# 8-8main.net
KiCad netlist of a schematic drawn in Altium Designer
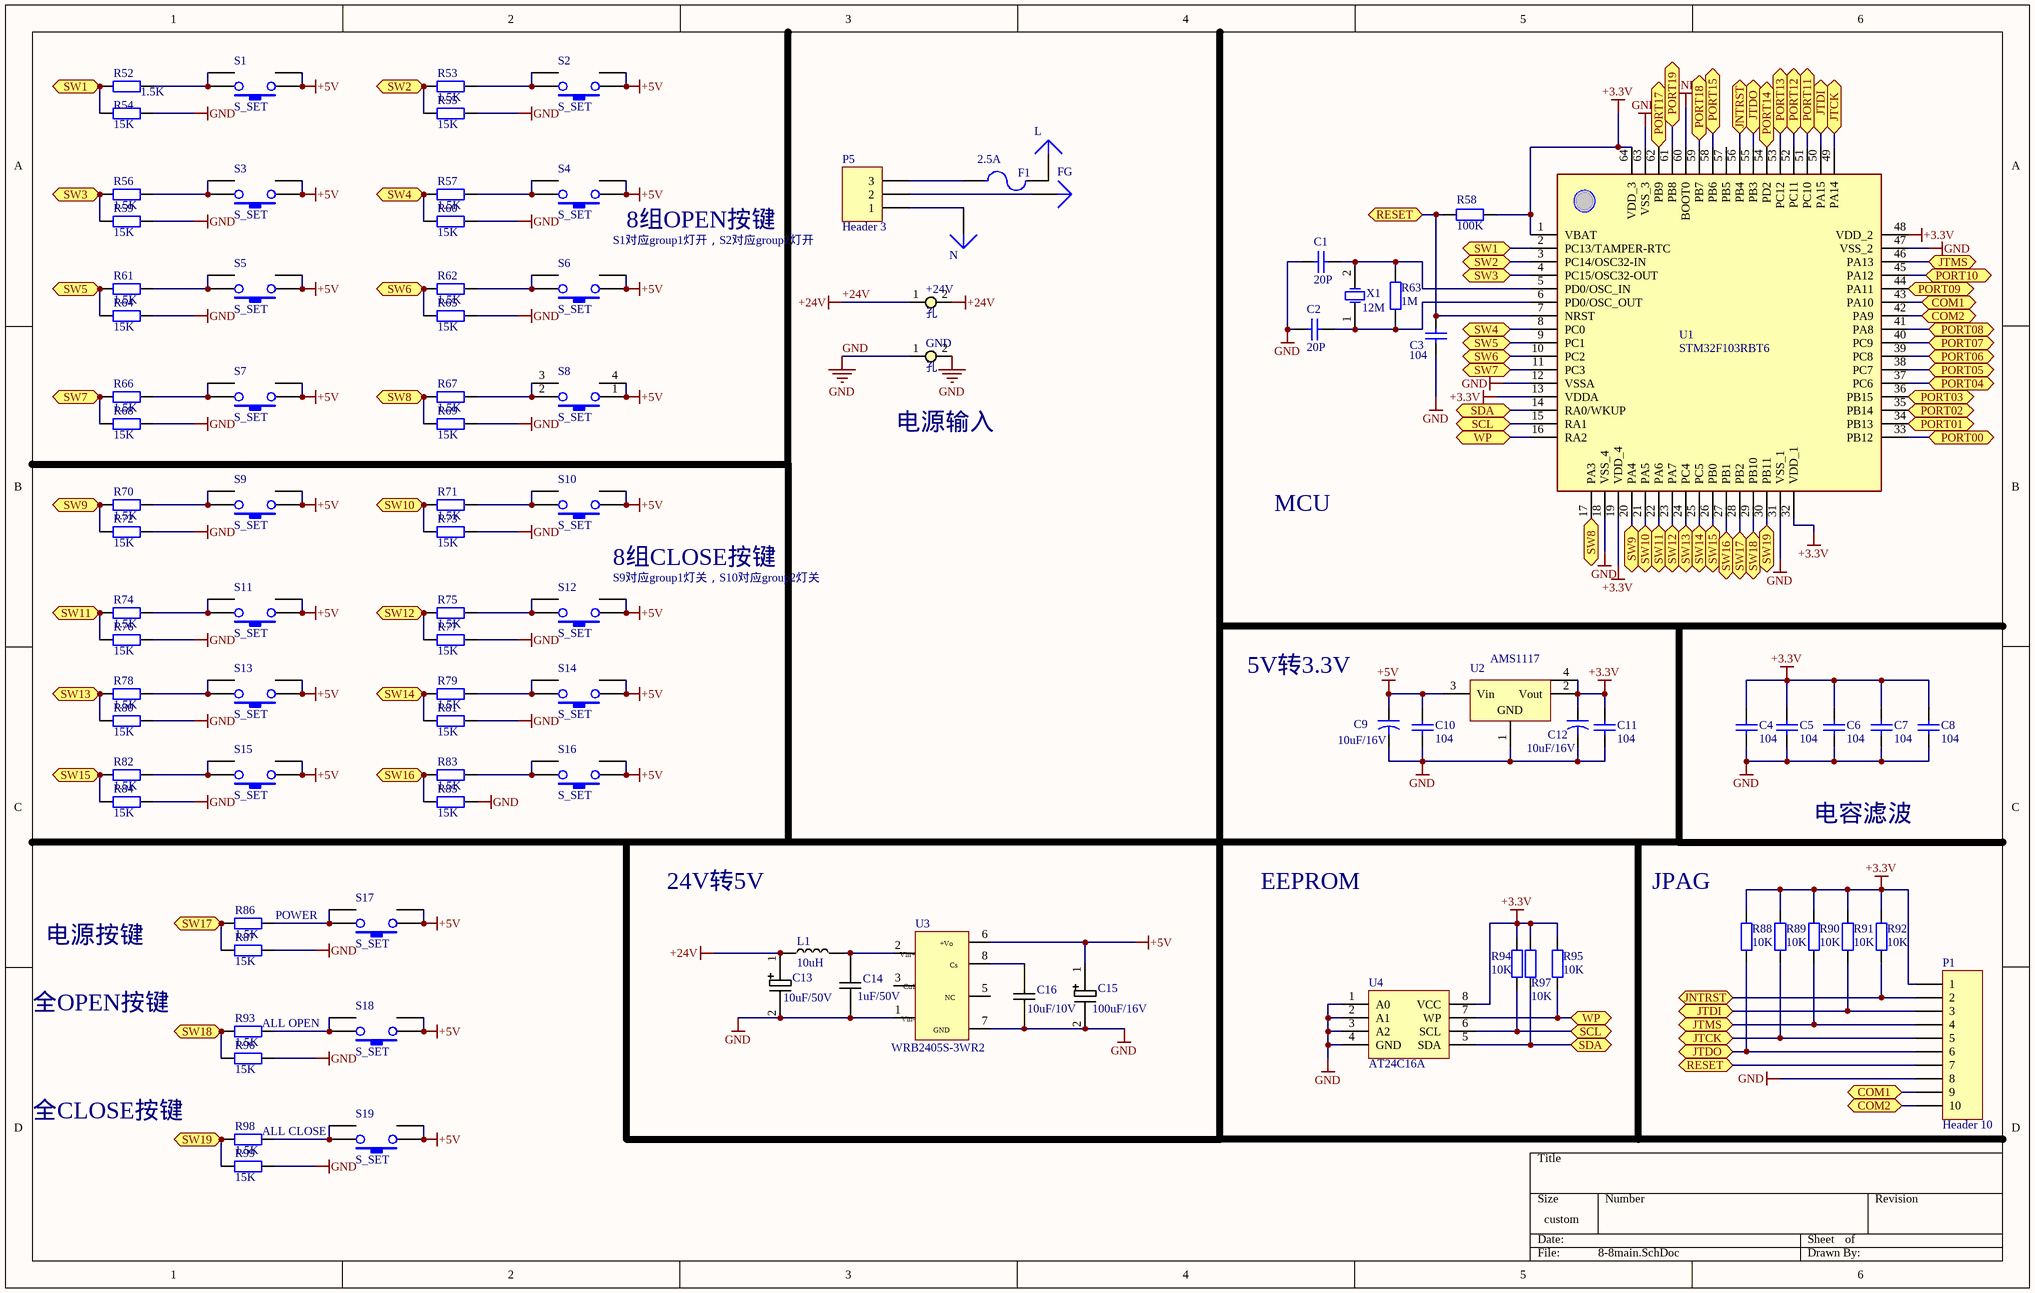
[diagram p0: 8-8main.SchDoc]

(export (version "E")
  (design (tool "Eeschema 10.0.6"))
  (components
    (comp (ref "+24V") (value "孔") (footprint "TIMECON2PIN5.1MMA") (libsource (lib "mylib") (part "安装孔3")))
    (comp (ref "C1")
      (value "20P")
      (footprint "0805 C")
      (description "Capacitor")
      (fields
        (field (name "MANUFACTURER") "Generic Components")
        (field (name "Comment") "Cap")
        (field (name "PUBLISHER") "Altium Hobart Technology Centre")
      )
      (libsource (lib "Miscellaneous Devices") (part "Cap"))
    )
    (comp (ref "C2")
      (value "20P")
      (footprint "0805 C")
      (description "Capacitor")
      (fields
        (field (name "MANUFACTURER") "Generic Components")
        (field (name "Comment") "Cap")
        (field (name "PUBLISHER") "Altium Hobart Technology Centre")
      )
      (libsource (lib "Miscellaneous Devices") (part "Cap"))
    )
    (comp (ref "C3")
      (value "104")
      (footprint "0805 C")
      (description "Capacitor")
      (fields
        (field (name "MANUFACTURER") "Generic Components")
        (field (name "Comment") "Cap")
        (field (name "PUBLISHER") "Altium Hobart Technology Centre")
      )
      (libsource (lib "Miscellaneous Devices") (part "Cap"))
    )
    (comp (ref "C4")
      (value "104")
      (footprint "0603 C")
      (description "Capacitor")
      (fields
        (field (name "MANUFACTURER") "Generic Components")
        (field (name "Comment") "Cap")
        (field (name "PUBLISHER") "Altium Hobart Technology Centre")
      )
      (libsource (lib "Miscellaneous Devices") (part "Cap"))
    )
    (comp (ref "C5")
      (value "104")
      (footprint "0603 C")
      (description "Capacitor")
      (fields
        (field (name "MANUFACTURER") "Generic Components")
        (field (name "Comment") "Cap")
        (field (name "PUBLISHER") "Altium Hobart Technology Centre")
      )
      (libsource (lib "Miscellaneous Devices") (part "Cap"))
    )
    (comp (ref "C6")
      (value "104")
      (footprint "0603 C")
      (description "Capacitor")
      (fields
        (field (name "MANUFACTURER") "Generic Components")
        (field (name "Comment") "Cap")
        (field (name "PUBLISHER") "Altium Hobart Technology Centre")
      )
      (libsource (lib "Miscellaneous Devices") (part "Cap"))
    )
    (comp (ref "C7")
      (value "104")
      (footprint "0603 C")
      (description "Capacitor")
      (fields
        (field (name "MANUFACTURER") "Generic Components")
        (field (name "Comment") "Cap")
        (field (name "PUBLISHER") "Altium Hobart Technology Centre")
      )
      (libsource (lib "Miscellaneous Devices") (part "Cap"))
    )
    (comp (ref "C8")
      (value "104")
      (footprint "0603 C")
      (description "Capacitor")
      (fields
        (field (name "MANUFACTURER") "Generic Components")
        (field (name "Comment") "Cap")
        (field (name "PUBLISHER") "Altium Hobart Technology Centre")
      )
      (libsource (lib "Miscellaneous Devices") (part "Cap"))
    )
    (comp (ref "C9")
      (value "10uF/16V")
      (footprint "0805 C")
      (description "Capacitor")
      (fields (field (name "PUBLISHER") "Altium Limited"))
      (libsource (lib "Miscellaneous Devices") (part "Cap2"))
    )
    (comp (ref "C10")
      (value "104")
      (footprint "0805 C")
      (description "Capacitor")
      (fields
        (field (name "MANUFACTURER") "Generic Components")
        (field (name "Comment") "Cap")
        (field (name "PUBLISHER") "Altium Hobart Technology Centre")
      )
      (libsource (lib "Miscellaneous Devices") (part "Cap"))
    )
    (comp (ref "C11")
      (value "104")
      (footprint "0805 C")
      (description "Capacitor")
      (fields
        (field (name "MANUFACTURER") "Generic Components")
        (field (name "Comment") "Cap")
        (field (name "PUBLISHER") "Altium Hobart Technology Centre")
      )
      (libsource (lib "Miscellaneous Devices") (part "Cap"))
    )
    (comp (ref "C12")
      (value "10uF/16V")
      (footprint "0805 C")
      (description "Capacitor")
      (fields (field (name "PUBLISHER") "Altium Limited"))
      (libsource (lib "Miscellaneous Devices") (part "Cap2"))
    )
    (comp (ref "C13")
      (value "10uF/50V")
      (footprint "C 10uF/50V")
      (fields (field (name "Comment") "CAP Al"))
      (libsource (lib "mylib") (part "CAP Al"))
    )
    (comp (ref "C14")
      (value "1uF/50V")
      (footprint "0805 C")
      (fields (field (name "Comment") "CAP"))
      (libsource (lib "mylib") (part "CAP"))
    )
    (comp (ref "C15")
      (value "100uF/16V")
      (footprint "C 100uF/16V φ5*11mm SIP")
      (fields (field (name "Comment") "CAP Al"))
      (libsource (lib "mylib") (part "CAP Al"))
    )
    (comp (ref "C16")
      (value "10uF/10V")
      (footprint "0805 C")
      (fields (field (name "Comment") "CAP"))
      (libsource (lib "mylib") (part "CAP"))
    )
    (comp (ref "F1")
      (value "2.5A")
      (footprint "1A/250V-1")
      (description "Fuse")
      (fields (field (name "PUBLISHER") "Altium Limited"))
      (libsource (lib "Miscellaneous Devices") (part "Fuse 2"))
    )
    (comp (ref "FG") (value "~") (footprint "VIA") (libsource (lib "*") (part "PLUG")))
    (comp (ref "GND") (value "孔") (footprint "TIMECON2PIN5.1MMA") (libsource (lib "mylib") (part "安装孔3")))
    (comp (ref "L") (value "~") (footprint "VIA") (libsource (lib "*") (part "PLUG")))
    (comp (ref "L1")
      (value "10uH")
      (footprint "L 2.2uH SMD")
      (fields (field (name "Comment") "Inductor"))
      (libsource (lib "mylib") (part "Inductor"))
    )
    (comp (ref "N") (value "~") (footprint "VIA") (libsource (lib "*") (part "PLUG")))
    (comp (ref "P1")
      (value "Header 10")
      (footprint "Header 2*5 SMD")
      (description "Header, 10-Pin")
      (fields (field (name "PUBLISHER") "Altium Limited"))
      (libsource (lib "Miscellaneous Connectors") (part "Header 10"))
    )
    (comp (ref "P5")
      (value "Header 3")
      (footprint "TIMECON3PIN5.1MMA")
      (description "Header, 3-Pin")
      (fields (field (name "PUBLISHER") "Altium Limited"))
      (libsource (lib "Miscellaneous Connectors") (part "Header 3"))
    )
    (comp (ref "R52")
      (value "1.5K")
      (footprint "0805 R 1/8W")
      (description "Resistor")
      (fields
        (field (name "MANUFACTURER") "Generic Components")
        (field (name "Comment") "Res2")
        (field (name "PUBLISHER") "Altium Hobart Technology Centre")
      )
      (libsource (lib "Miscellaneous Devices") (part "Res2"))
    )
    (comp (ref "R53")
      (value "1.5K")
      (footprint "0805 R 1/8W")
      (description "Resistor")
      (fields
        (field (name "MANUFACTURER") "Generic Components")
        (field (name "Comment") "Res2")
        (field (name "PUBLISHER") "Altium Hobart Technology Centre")
      )
      (libsource (lib "Miscellaneous Devices") (part "Res2"))
    )
    (comp (ref "R54")
      (value "15K")
      (footprint "0805 R 1/8W")
      (description "Resistor")
      (fields
        (field (name "MANUFACTURER") "Generic Components")
        (field (name "Comment") "Res2")
        (field (name "PUBLISHER") "Altium Hobart Technology Centre")
      )
      (libsource (lib "Miscellaneous Devices") (part "Res2"))
    )
    (comp (ref "R55")
      (value "15K")
      (footprint "0805 R 1/8W")
      (description "Resistor")
      (fields
        (field (name "MANUFACTURER") "Generic Components")
        (field (name "Comment") "Res2")
        (field (name "PUBLISHER") "Altium Hobart Technology Centre")
      )
      (libsource (lib "Miscellaneous Devices") (part "Res2"))
    )
    (comp (ref "R56")
      (value "1.5K")
      (footprint "0805 R 1/8W")
      (description "Resistor")
      (fields
        (field (name "MANUFACTURER") "Generic Components")
        (field (name "Comment") "Res2")
        (field (name "PUBLISHER") "Altium Hobart Technology Centre")
      )
      (libsource (lib "Miscellaneous Devices") (part "Res2"))
    )
    (comp (ref "R57")
      (value "1.5K")
      (footprint "0805 R 1/8W")
      (description "Resistor")
      (fields
        (field (name "MANUFACTURER") "Generic Components")
        (field (name "Comment") "Res2")
        (field (name "PUBLISHER") "Altium Hobart Technology Centre")
      )
      (libsource (lib "Miscellaneous Devices") (part "Res2"))
    )
    (comp (ref "R58")
      (value "100K")
      (footprint "0805 R 1/8W")
      (description "Resistor")
      (fields
        (field (name "MANUFACTURER") "Generic Components")
        (field (name "Comment") "Res2")
        (field (name "PUBLISHER") "Altium Hobart Technology Centre")
      )
      (libsource (lib "") (part "Res2_3"))
    )
    (comp (ref "R59")
      (value "15K")
      (footprint "0805 R 1/8W")
      (description "Resistor")
      (fields
        (field (name "MANUFACTURER") "Generic Components")
        (field (name "Comment") "Res2")
        (field (name "PUBLISHER") "Altium Hobart Technology Centre")
      )
      (libsource (lib "Miscellaneous Devices") (part "Res2"))
    )
    (comp (ref "R60")
      (value "15K")
      (footprint "0805 R 1/8W")
      (description "Resistor")
      (fields
        (field (name "MANUFACTURER") "Generic Components")
        (field (name "Comment") "Res2")
        (field (name "PUBLISHER") "Altium Hobart Technology Centre")
      )
      (libsource (lib "Miscellaneous Devices") (part "Res2"))
    )
    (comp (ref "R61")
      (value "1.5K")
      (footprint "0805 R 1/8W")
      (description "Resistor")
      (fields
        (field (name "MANUFACTURER") "Generic Components")
        (field (name "Comment") "Res2")
        (field (name "PUBLISHER") "Altium Hobart Technology Centre")
      )
      (libsource (lib "Miscellaneous Devices") (part "Res2"))
    )
    (comp (ref "R62")
      (value "1.5K")
      (footprint "0805 R 1/8W")
      (description "Resistor")
      (fields
        (field (name "MANUFACTURER") "Generic Components")
        (field (name "Comment") "Res2")
        (field (name "PUBLISHER") "Altium Hobart Technology Centre")
      )
      (libsource (lib "Miscellaneous Devices") (part "Res2"))
    )
    (comp (ref "R63")
      (value "1M")
      (footprint "0805 R 1/8W")
      (description "Resistor")
      (fields
        (field (name "MANUFACTURER") "Generic Components")
        (field (name "Comment") "Res2")
        (field (name "PUBLISHER") "Altium Hobart Technology Centre")
      )
      (libsource (lib "") (part "Res2_2"))
    )
    (comp (ref "R64")
      (value "15K")
      (footprint "0805 R 1/8W")
      (description "Resistor")
      (fields
        (field (name "MANUFACTURER") "Generic Components")
        (field (name "Comment") "Res2")
        (field (name "PUBLISHER") "Altium Hobart Technology Centre")
      )
      (libsource (lib "Miscellaneous Devices") (part "Res2"))
    )
    (comp (ref "R65")
      (value "15K")
      (footprint "0805 R 1/8W")
      (description "Resistor")
      (fields
        (field (name "MANUFACTURER") "Generic Components")
        (field (name "Comment") "Res2")
        (field (name "PUBLISHER") "Altium Hobart Technology Centre")
      )
      (libsource (lib "Miscellaneous Devices") (part "Res2"))
    )
    (comp (ref "R66")
      (value "1.5K")
      (footprint "0805 R 1/8W")
      (description "Resistor")
      (fields
        (field (name "MANUFACTURER") "Generic Components")
        (field (name "Comment") "Res2")
        (field (name "PUBLISHER") "Altium Hobart Technology Centre")
      )
      (libsource (lib "Miscellaneous Devices") (part "Res2"))
    )
    (comp (ref "R67")
      (value "1.5K")
      (footprint "0805 R 1/8W")
      (description "Resistor")
      (fields
        (field (name "MANUFACTURER") "Generic Components")
        (field (name "Comment") "Res2")
        (field (name "PUBLISHER") "Altium Hobart Technology Centre")
      )
      (libsource (lib "Miscellaneous Devices") (part "Res2"))
    )
    (comp (ref "R68")
      (value "15K")
      (footprint "0805 R 1/8W")
      (description "Resistor")
      (fields
        (field (name "MANUFACTURER") "Generic Components")
        (field (name "Comment") "Res2")
        (field (name "PUBLISHER") "Altium Hobart Technology Centre")
      )
      (libsource (lib "Miscellaneous Devices") (part "Res2"))
    )
    (comp (ref "R69")
      (value "15K")
      (footprint "0805 R 1/8W")
      (description "Resistor")
      (fields
        (field (name "MANUFACTURER") "Generic Components")
        (field (name "Comment") "Res2")
        (field (name "PUBLISHER") "Altium Hobart Technology Centre")
      )
      (libsource (lib "Miscellaneous Devices") (part "Res2"))
    )
    (comp (ref "R70")
      (value "1.5K")
      (footprint "0805 R 1/8W")
      (description "Resistor")
      (fields
        (field (name "MANUFACTURER") "Generic Components")
        (field (name "Comment") "Res2")
        (field (name "PUBLISHER") "Altium Hobart Technology Centre")
      )
      (libsource (lib "Miscellaneous Devices") (part "Res2"))
    )
    (comp (ref "R71")
      (value "1.5K")
      (footprint "0805 R 1/8W")
      (description "Resistor")
      (fields
        (field (name "MANUFACTURER") "Generic Components")
        (field (name "Comment") "Res2")
        (field (name "PUBLISHER") "Altium Hobart Technology Centre")
      )
      (libsource (lib "Miscellaneous Devices") (part "Res2"))
    )
    (comp (ref "R72")
      (value "15K")
      (footprint "0805 R 1/8W")
      (description "Resistor")
      (fields
        (field (name "MANUFACTURER") "Generic Components")
        (field (name "Comment") "Res2")
        (field (name "PUBLISHER") "Altium Hobart Technology Centre")
      )
      (libsource (lib "Miscellaneous Devices") (part "Res2"))
    )
    (comp (ref "R73")
      (value "15K")
      (footprint "0805 R 1/8W")
      (description "Resistor")
      (fields
        (field (name "MANUFACTURER") "Generic Components")
        (field (name "Comment") "Res2")
        (field (name "PUBLISHER") "Altium Hobart Technology Centre")
      )
      (libsource (lib "Miscellaneous Devices") (part "Res2"))
    )
    (comp (ref "R74")
      (value "1.5K")
      (footprint "0805 R 1/8W")
      (description "Resistor")
      (fields
        (field (name "MANUFACTURER") "Generic Components")
        (field (name "Comment") "Res2")
        (field (name "PUBLISHER") "Altium Hobart Technology Centre")
      )
      (libsource (lib "Miscellaneous Devices") (part "Res2"))
    )
    (comp (ref "R75")
      (value "1.5K")
      (footprint "0805 R 1/8W")
      (description "Resistor")
      (fields
        (field (name "MANUFACTURER") "Generic Components")
        (field (name "Comment") "Res2")
        (field (name "PUBLISHER") "Altium Hobart Technology Centre")
      )
      (libsource (lib "Miscellaneous Devices") (part "Res2"))
    )
    (comp (ref "R76")
      (value "15K")
      (footprint "0805 R 1/8W")
      (description "Resistor")
      (fields
        (field (name "MANUFACTURER") "Generic Components")
        (field (name "Comment") "Res2")
        (field (name "PUBLISHER") "Altium Hobart Technology Centre")
      )
      (libsource (lib "Miscellaneous Devices") (part "Res2"))
    )
    (comp (ref "R77")
      (value "15K")
      (footprint "0805 R 1/8W")
      (description "Resistor")
      (fields
        (field (name "MANUFACTURER") "Generic Components")
        (field (name "Comment") "Res2")
        (field (name "PUBLISHER") "Altium Hobart Technology Centre")
      )
      (libsource (lib "Miscellaneous Devices") (part "Res2"))
    )
    (comp (ref "R78")
      (value "1.5K")
      (footprint "0805 R 1/8W")
      (description "Resistor")
      (fields
        (field (name "MANUFACTURER") "Generic Components")
        (field (name "Comment") "Res2")
        (field (name "PUBLISHER") "Altium Hobart Technology Centre")
      )
      (libsource (lib "Miscellaneous Devices") (part "Res2"))
    )
    (comp (ref "R79")
      (value "1.5K")
      (footprint "0805 R 1/8W")
      (description "Resistor")
      (fields
        (field (name "MANUFACTURER") "Generic Components")
        (field (name "Comment") "Res2")
        (field (name "PUBLISHER") "Altium Hobart Technology Centre")
      )
      (libsource (lib "Miscellaneous Devices") (part "Res2"))
    )
    (comp (ref "R80")
      (value "15K")
      (footprint "0805 R 1/8W")
      (description "Resistor")
      (fields
        (field (name "MANUFACTURER") "Generic Components")
        (field (name "Comment") "Res2")
        (field (name "PUBLISHER") "Altium Hobart Technology Centre")
      )
      (libsource (lib "Miscellaneous Devices") (part "Res2"))
    )
    (comp (ref "R81")
      (value "15K")
      (footprint "0805 R 1/8W")
      (description "Resistor")
      (fields
        (field (name "MANUFACTURER") "Generic Components")
        (field (name "Comment") "Res2")
        (field (name "PUBLISHER") "Altium Hobart Technology Centre")
      )
      (libsource (lib "Miscellaneous Devices") (part "Res2"))
    )
    (comp (ref "R82")
      (value "1.5K")
      (footprint "0805 R 1/8W")
      (description "Resistor")
      (fields
        (field (name "MANUFACTURER") "Generic Components")
        (field (name "Comment") "Res2")
        (field (name "PUBLISHER") "Altium Hobart Technology Centre")
      )
      (libsource (lib "Miscellaneous Devices") (part "Res2"))
    )
    (comp (ref "R83")
      (value "1.5K")
      (footprint "0805 R 1/8W")
      (description "Resistor")
      (fields
        (field (name "MANUFACTURER") "Generic Components")
        (field (name "Comment") "Res2")
        (field (name "PUBLISHER") "Altium Hobart Technology Centre")
      )
      (libsource (lib "Miscellaneous Devices") (part "Res2"))
    )
    (comp (ref "R84")
      (value "15K")
      (footprint "0805 R 1/8W")
      (description "Resistor")
      (fields
        (field (name "MANUFACTURER") "Generic Components")
        (field (name "Comment") "Res2")
        (field (name "PUBLISHER") "Altium Hobart Technology Centre")
      )
      (libsource (lib "Miscellaneous Devices") (part "Res2"))
    )
    (comp (ref "R85")
      (value "15K")
      (footprint "0805 R 1/8W")
      (description "Resistor")
      (fields
        (field (name "MANUFACTURER") "Generic Components")
        (field (name "Comment") "Res2")
        (field (name "PUBLISHER") "Altium Hobart Technology Centre")
      )
      (libsource (lib "Miscellaneous Devices") (part "Res2"))
    )
    (comp (ref "R86")
      (value "1.5K")
      (footprint "0805 R 1/8W")
      (description "Resistor")
      (fields
        (field (name "MANUFACTURER") "Generic Components")
        (field (name "Comment") "Res2")
        (field (name "PUBLISHER") "Altium Hobart Technology Centre")
      )
      (libsource (lib "Miscellaneous Devices") (part "Res2"))
    )
    (comp (ref "R87")
      (value "15K")
      (footprint "0805 R 1/8W")
      (description "Resistor")
      (fields
        (field (name "MANUFACTURER") "Generic Components")
        (field (name "Comment") "Res2")
        (field (name "PUBLISHER") "Altium Hobart Technology Centre")
      )
      (libsource (lib "Miscellaneous Devices") (part "Res2"))
    )
    (comp (ref "R88")
      (value "10K")
      (footprint "0805 R 1/8W")
      (description "Resistor")
      (fields
        (field (name "MANUFACTURER") "Generic Components")
        (field (name "Comment") "Res2")
        (field (name "PUBLISHER") "Altium Hobart Technology Centre")
      )
      (libsource (lib "") (part "Res2_1"))
    )
    (comp (ref "R89")
      (value "10K")
      (footprint "0805 R 1/8W")
      (description "Resistor")
      (fields
        (field (name "MANUFACTURER") "Generic Components")
        (field (name "Comment") "Res2")
        (field (name "PUBLISHER") "Altium Hobart Technology Centre")
      )
      (libsource (lib "") (part "Res2_1"))
    )
    (comp (ref "R90")
      (value "10K")
      (footprint "0805 R 1/8W")
      (description "Resistor")
      (fields
        (field (name "MANUFACTURER") "Generic Components")
        (field (name "Comment") "Res2")
        (field (name "PUBLISHER") "Altium Hobart Technology Centre")
      )
      (libsource (lib "") (part "Res2_1"))
    )
    (comp (ref "R91")
      (value "10K")
      (footprint "0805 R 1/8W")
      (description "Resistor")
      (fields
        (field (name "MANUFACTURER") "Generic Components")
        (field (name "Comment") "Res2")
        (field (name "PUBLISHER") "Altium Hobart Technology Centre")
      )
      (libsource (lib "") (part "Res2_1"))
    )
    (comp (ref "R92")
      (value "10K")
      (footprint "0805 R 1/8W")
      (description "Resistor")
      (fields
        (field (name "MANUFACTURER") "Generic Components")
        (field (name "Comment") "Res2")
        (field (name "PUBLISHER") "Altium Hobart Technology Centre")
      )
      (libsource (lib "") (part "Res2_1"))
    )
    (comp (ref "R93")
      (value "1.5K")
      (footprint "0805 R 1/8W")
      (description "Resistor")
      (fields
        (field (name "MANUFACTURER") "Generic Components")
        (field (name "Comment") "Res2")
        (field (name "PUBLISHER") "Altium Hobart Technology Centre")
      )
      (libsource (lib "Miscellaneous Devices") (part "Res2"))
    )
    (comp (ref "R94")
      (value "10K")
      (footprint "0805 R 1/8W")
      (description "Resistor")
      (fields
        (field (name "MANUFACTURER") "Generic Components")
        (field (name "Comment") "Res2")
        (field (name "PUBLISHER") "Altium Hobart Technology Centre")
      )
      (libsource (lib "") (part "Res2_1"))
    )
    (comp (ref "R95")
      (value "10K")
      (footprint "0805 R 1/8W")
      (description "Resistor")
      (fields
        (field (name "MANUFACTURER") "Generic Components")
        (field (name "Comment") "Res2")
        (field (name "PUBLISHER") "Altium Hobart Technology Centre")
      )
      (libsource (lib "") (part "Res2_1"))
    )
    (comp (ref "R96")
      (value "15K")
      (footprint "0805 R 1/8W")
      (description "Resistor")
      (fields
        (field (name "MANUFACTURER") "Generic Components")
        (field (name "Comment") "Res2")
        (field (name "PUBLISHER") "Altium Hobart Technology Centre")
      )
      (libsource (lib "Miscellaneous Devices") (part "Res2"))
    )
    (comp (ref "R97")
      (value "10K")
      (footprint "0805 R 1/8W")
      (description "Resistor")
      (fields
        (field (name "MANUFACTURER") "Generic Components")
        (field (name "Comment") "Res2")
        (field (name "PUBLISHER") "Altium Hobart Technology Centre")
      )
      (libsource (lib "") (part "Res2_1"))
    )
    (comp (ref "R98")
      (value "1.5K")
      (footprint "0805 R 1/8W")
      (description "Resistor")
      (fields
        (field (name "MANUFACTURER") "Generic Components")
        (field (name "Comment") "Res2")
        (field (name "PUBLISHER") "Altium Hobart Technology Centre")
      )
      (libsource (lib "Miscellaneous Devices") (part "Res2"))
    )
    (comp (ref "R99")
      (value "15K")
      (footprint "0805 R 1/8W")
      (description "Resistor")
      (fields
        (field (name "MANUFACTURER") "Generic Components")
        (field (name "Comment") "Res2")
        (field (name "PUBLISHER") "Altium Hobart Technology Centre")
      )
      (libsource (lib "Miscellaneous Devices") (part "Res2"))
    )
    (comp (ref "S1")
      (value "S_SET")
      (footprint "12*12*4.3")
      (libsource (lib "ABIDO 301UL Display") (part "SW-PB"))
    )
    (comp (ref "S2")
      (value "S_SET")
      (footprint "12*12*4.3")
      (libsource (lib "ABIDO 301UL Display") (part "SW-PB"))
    )
    (comp (ref "S3")
      (value "S_SET")
      (footprint "12*12*4.3")
      (libsource (lib "ABIDO 301UL Display") (part "SW-PB"))
    )
    (comp (ref "S4")
      (value "S_SET")
      (footprint "12*12*4.3")
      (libsource (lib "ABIDO 301UL Display") (part "SW-PB"))
    )
    (comp (ref "S5")
      (value "S_SET")
      (footprint "12*12*4.3")
      (libsource (lib "ABIDO 301UL Display") (part "SW-PB"))
    )
    (comp (ref "S6")
      (value "S_SET")
      (footprint "12*12*4.3")
      (libsource (lib "ABIDO 301UL Display") (part "SW-PB"))
    )
    (comp (ref "S7")
      (value "S_SET")
      (footprint "12*12*4.3")
      (libsource (lib "ABIDO 301UL Display") (part "SW-PB"))
    )
    (comp (ref "S8") (value "S_SET") (footprint "12*12*4.3") (libsource (lib "") (part "SW-PB_1")))
    (comp (ref "S9")
      (value "S_SET")
      (footprint "12*12*4.3")
      (libsource (lib "ABIDO 301UL Display") (part "SW-PB"))
    )
    (comp (ref "S10")
      (value "S_SET")
      (footprint "12*12*4.3")
      (libsource (lib "ABIDO 301UL Display") (part "SW-PB"))
    )
    (comp (ref "S11")
      (value "S_SET")
      (footprint "12*12*4.3")
      (libsource (lib "ABIDO 301UL Display") (part "SW-PB"))
    )
    (comp (ref "S12")
      (value "S_SET")
      (footprint "12*12*4.3")
      (libsource (lib "ABIDO 301UL Display") (part "SW-PB"))
    )
    (comp (ref "S13")
      (value "S_SET")
      (footprint "12*12*4.3")
      (libsource (lib "ABIDO 301UL Display") (part "SW-PB"))
    )
    (comp (ref "S14")
      (value "S_SET")
      (footprint "12*12*4.3")
      (libsource (lib "ABIDO 301UL Display") (part "SW-PB"))
    )
    (comp (ref "S15")
      (value "S_SET")
      (footprint "12*12*4.3")
      (libsource (lib "ABIDO 301UL Display") (part "SW-PB"))
    )
    (comp (ref "S16")
      (value "S_SET")
      (footprint "12*12*4.3")
      (libsource (lib "ABIDO 301UL Display") (part "SW-PB"))
    )
    (comp (ref "S17")
      (value "S_SET")
      (footprint "12*12*4.3")
      (libsource (lib "ABIDO 301UL Display") (part "SW-PB"))
    )
    (comp (ref "S18")
      (value "S_SET")
      (footprint "12*12*4.3")
      (libsource (lib "ABIDO 301UL Display") (part "SW-PB"))
    )
    (comp (ref "S19")
      (value "S_SET")
      (footprint "12*12*4.3")
      (libsource (lib "ABIDO 301UL Display") (part "SW-PB"))
    )
    (comp (ref "U1")
      (value "STM32F103RBT6")
      (footprint "STM32F103RBT6")
      (libsource (lib "MYLIB") (part "STM32F103R8T6"))
    )
    (comp (ref "U2")
      (value "AMS1117")
      (footprint "SOT223_L")
      (description "Voltage Regulator")
      (fields (field (name "PUBLISHER") "Altium Limited"))
      (libsource (lib "ABIDO 301UL Control") (part "Volt Reg"))
    )
    (comp (ref "U3")
      (value "WRB2405S-3WR2")
      (footprint "WRB_S-3WR2")
      (libsource (lib "mylib") (part "WRB2405S-3WR2"))
    )
    (comp (ref "U4") (value "AT24C16A") (footprint "SOIC") (libsource (lib "MYLIB") (part "AT24C16A")))
    (comp (ref "X1")
      (value "12M")
      (footprint "XTAL SMD")
      (description "Crystal Oscillator")
      (fields
        (field (name "MANUFACTURER") "Generic Components")
        (field (name "PUBLISHER") "Altium Hobart Technology Centre")
      )
      (libsource (lib "Miscellaneous Devices") (part "XTAL"))
    )
  )
  (nets
    (net (code "1") (name "+3.3V") (class "Default")
      (node (ref "C11") (pin "1") (pinfunction "1_1") (pintype "passive"))
      (node (ref "C12") (pin "1") (pinfunction "1_1") (pintype "passive"))
      (node (ref "C4") (pin "1") (pinfunction "1_1") (pintype "passive"))
      (node (ref "C5") (pin "1") (pinfunction "1_1") (pintype "passive"))
      (node (ref "C6") (pin "1") (pinfunction "1_1") (pintype "passive"))
      (node (ref "C7") (pin "1") (pinfunction "1_1") (pintype "passive"))
      (node (ref "C8") (pin "1") (pinfunction "1_1") (pintype "passive"))
      (node (ref "P1") (pin "1") (pinfunction "1_1") (pintype "passive"))
      (node (ref "R58") (pin "2") (pinfunction "2_2") (pintype "passive"))
      (node (ref "R88") (pin "2") (pinfunction "2_2") (pintype "passive"))
      (node (ref "R89") (pin "2") (pinfunction "2_2") (pintype "passive"))
      (node (ref "R90") (pin "2") (pinfunction "2_2") (pintype "passive"))
      (node (ref "R91") (pin "2") (pinfunction "2_2") (pintype "passive"))
      (node (ref "R92") (pin "2") (pinfunction "2_2") (pintype "passive"))
      (node (ref "R94") (pin "2") (pinfunction "2_2") (pintype "passive"))
      (node (ref "R95") (pin "2") (pinfunction "2_2") (pintype "passive"))
      (node (ref "R97") (pin "2") (pinfunction "2_2") (pintype "passive"))
      (node (ref "U1") (pin "1") (pinfunction "VBAT_1") (pintype "passive"))
      (node (ref "U1") (pin "13") (pinfunction "VDDA_13") (pintype "passive"))
      (node (ref "U1") (pin "19") (pinfunction "VDD_4_19") (pintype "passive"))
      (node (ref "U1") (pin "32") (pinfunction "VDD_1_32") (pintype "passive"))
      (node (ref "U1") (pin "48") (pinfunction "VDD_2_48") (pintype "passive"))
      (node (ref "U1") (pin "64") (pinfunction "VDD_3_64") (pintype "passive"))
      (node (ref "U2") (pin "2") (pinfunction "Vout_2") (pintype "passive"))
      (node (ref "U2") (pin "4") (pinfunction "Vout_4") (pintype "passive"))
      (node (ref "U4") (pin "8") (pinfunction "VCC_8") (pintype "passive"))
    )
    (net (code "2") (name "+5V") (class "Default")
      (node (ref "C10") (pin "1") (pinfunction "1_1") (pintype "passive"))
      (node (ref "C15") (pin "1") (pinfunction "1_1") (pintype "passive"))
      (node (ref "C9") (pin "1") (pinfunction "1_1") (pintype "passive"))
      (node (ref "S1") (pin "1") (pinfunction "1_1") (pintype "passive"))
      (node (ref "S1") (pin "4") (pinfunction "4_4") (pintype "passive"))
      (node (ref "S10") (pin "1") (pinfunction "1_1") (pintype "passive"))
      (node (ref "S10") (pin "4") (pinfunction "4_4") (pintype "passive"))
      (node (ref "S11") (pin "1") (pinfunction "1_1") (pintype "passive"))
      (node (ref "S11") (pin "4") (pinfunction "4_4") (pintype "passive"))
      (node (ref "S12") (pin "1") (pinfunction "1_1") (pintype "passive"))
      (node (ref "S12") (pin "4") (pinfunction "4_4") (pintype "passive"))
      (node (ref "S13") (pin "1") (pinfunction "1_1") (pintype "passive"))
      (node (ref "S13") (pin "4") (pinfunction "4_4") (pintype "passive"))
      (node (ref "S14") (pin "1") (pinfunction "1_1") (pintype "passive"))
      (node (ref "S14") (pin "4") (pinfunction "4_4") (pintype "passive"))
      (node (ref "S15") (pin "1") (pinfunction "1_1") (pintype "passive"))
      (node (ref "S15") (pin "4") (pinfunction "4_4") (pintype "passive"))
      (node (ref "S16") (pin "1") (pinfunction "1_1") (pintype "passive"))
      (node (ref "S16") (pin "4") (pinfunction "4_4") (pintype "passive"))
      (node (ref "S17") (pin "1") (pinfunction "1_1") (pintype "passive"))
      (node (ref "S17") (pin "4") (pinfunction "4_4") (pintype "passive"))
      (node (ref "S18") (pin "1") (pinfunction "1_1") (pintype "passive"))
      (node (ref "S18") (pin "4") (pinfunction "4_4") (pintype "passive"))
      (node (ref "S19") (pin "1") (pinfunction "1_1") (pintype "passive"))
      (node (ref "S19") (pin "4") (pinfunction "4_4") (pintype "passive"))
      (node (ref "S2") (pin "1") (pinfunction "1_1") (pintype "passive"))
      (node (ref "S2") (pin "4") (pinfunction "4_4") (pintype "passive"))
      (node (ref "S3") (pin "1") (pinfunction "1_1") (pintype "passive"))
      (node (ref "S3") (pin "4") (pinfunction "4_4") (pintype "passive"))
      (node (ref "S4") (pin "1") (pinfunction "1_1") (pintype "passive"))
      (node (ref "S4") (pin "4") (pinfunction "4_4") (pintype "passive"))
      (node (ref "S5") (pin "1") (pinfunction "1_1") (pintype "passive"))
      (node (ref "S5") (pin "4") (pinfunction "4_4") (pintype "passive"))
      (node (ref "S6") (pin "1") (pinfunction "1_1") (pintype "passive"))
      (node (ref "S6") (pin "4") (pinfunction "4_4") (pintype "passive"))
      (node (ref "S7") (pin "1") (pinfunction "1_1") (pintype "passive"))
      (node (ref "S7") (pin "4") (pinfunction "4_4") (pintype "passive"))
      (node (ref "S8") (pin "1") (pinfunction "1_1") (pintype "passive"))
      (node (ref "S8") (pin "4") (pinfunction "4_4") (pintype "passive"))
      (node (ref "S9") (pin "1") (pinfunction "1_1") (pintype "passive"))
      (node (ref "S9") (pin "4") (pinfunction "4_4") (pintype "passive"))
      (node (ref "U2") (pin "3") (pinfunction "Vin_3") (pintype "passive"))
      (node (ref "U3") (pin "6") (pinfunction "6_6") (pintype "passive"))
    )
    (net (code "3") (name "+24V") (class "Default")
      (node (ref "+24V") (pin "1") (pinfunction "1_1") (pintype "passive"))
      (node (ref "+24V") (pin "2") (pinfunction "2_2") (pintype "passive"))
      (node (ref "C13") (pin "1") (pinfunction "1_1") (pintype "passive"))
      (node (ref "L1") (pin "1") (pinfunction "1_1") (pintype "passive"))
    )
    (net (code "4") (name "/COM1") (class "Default")
      (node (ref "P1") (pin "9") (pinfunction "9_9") (pintype "passive"))
      (node (ref "U1") (pin "43") (pinfunction "PA10_43") (pintype "passive"))
    )
    (net (code "5") (name "/COM2") (class "Default")
      (node (ref "P1") (pin "10") (pinfunction "10_10") (pintype "passive"))
      (node (ref "U1") (pin "42") (pinfunction "PA9_42") (pintype "passive"))
    )
    (net (code "6") (name "/JNTRST") (class "Default")
      (node (ref "P1") (pin "2") (pinfunction "2_2") (pintype "passive"))
      (node (ref "R92") (pin "1") (pinfunction "1_1") (pintype "passive"))
      (node (ref "U1") (pin "56") (pinfunction "PB4_56") (pintype "passive"))
    )
    (net (code "7") (name "/JTCK") (class "Default")
      (node (ref "P1") (pin "5") (pinfunction "5_5") (pintype "passive"))
      (node (ref "R89") (pin "1") (pinfunction "1_1") (pintype "passive"))
      (node (ref "U1") (pin "49") (pinfunction "PA14_49") (pintype "passive"))
    )
    (net (code "8") (name "/JTDI") (class "Default")
      (node (ref "P1") (pin "3") (pinfunction "3_3") (pintype "passive"))
      (node (ref "R91") (pin "1") (pinfunction "1_1") (pintype "passive"))
      (node (ref "U1") (pin "50") (pinfunction "PA15_50") (pintype "passive"))
    )
    (net (code "9") (name "/JTDO") (class "Default")
      (node (ref "P1") (pin "6") (pinfunction "6_6") (pintype "passive"))
      (node (ref "R88") (pin "1") (pinfunction "1_1") (pintype "passive"))
      (node (ref "U1") (pin "55") (pinfunction "PB3_55") (pintype "passive"))
    )
    (net (code "10") (name "/JTMS") (class "Default")
      (node (ref "P1") (pin "4") (pinfunction "4_4") (pintype "passive"))
      (node (ref "R90") (pin "1") (pinfunction "1_1") (pintype "passive"))
      (node (ref "U1") (pin "46") (pinfunction "PA13_46") (pintype "passive"))
    )
    (net (code "11") (name "/PORT00") (class "Default")
      (node (ref "U1") (pin "33") (pinfunction "PB12_33") (pintype "passive"))
    )
    (net (code "12") (name "/PORT01") (class "Default")
      (node (ref "U1") (pin "34") (pinfunction "PB13_34") (pintype "passive"))
    )
    (net (code "13") (name "/PORT02") (class "Default")
      (node (ref "U1") (pin "35") (pinfunction "PB14_35") (pintype "passive"))
    )
    (net (code "14") (name "/PORT03") (class "Default")
      (node (ref "U1") (pin "36") (pinfunction "PB15_36") (pintype "passive"))
    )
    (net (code "15") (name "/PORT04") (class "Default")
      (node (ref "U1") (pin "37") (pinfunction "PC6_37") (pintype "passive"))
    )
    (net (code "16") (name "/PORT05") (class "Default")
      (node (ref "U1") (pin "38") (pinfunction "PC7_38") (pintype "passive"))
    )
    (net (code "17") (name "/PORT06") (class "Default")
      (node (ref "U1") (pin "39") (pinfunction "PC8_39") (pintype "passive"))
    )
    (net (code "18") (name "/PORT07") (class "Default")
      (node (ref "U1") (pin "40") (pinfunction "PC9_40") (pintype "passive"))
    )
    (net (code "19") (name "/PORT08") (class "Default")
      (node (ref "U1") (pin "41") (pinfunction "PA8_41") (pintype "passive"))
    )
    (net (code "20") (name "/PORT09") (class "Default")
      (node (ref "U1") (pin "44") (pinfunction "PA11_44") (pintype "passive"))
    )
    (net (code "21") (name "/PORT10") (class "Default")
      (node (ref "U1") (pin "45") (pinfunction "PA12_45") (pintype "passive"))
    )
    (net (code "22") (name "/PORT11") (class "Default")
      (node (ref "U1") (pin "51") (pinfunction "PC10_51") (pintype "passive"))
    )
    (net (code "23") (name "/PORT12") (class "Default")
      (node (ref "U1") (pin "52") (pinfunction "PC11_52") (pintype "passive"))
    )
    (net (code "24") (name "/PORT13") (class "Default")
      (node (ref "U1") (pin "53") (pinfunction "PC12_53") (pintype "passive"))
    )
    (net (code "25") (name "/PORT14") (class "Default")
      (node (ref "U1") (pin "54") (pinfunction "PD2_54") (pintype "passive"))
    )
    (net (code "26") (name "/PORT15") (class "Default")
      (node (ref "U1") (pin "58") (pinfunction "PB6_58") (pintype "passive"))
    )
    (net (code "27") (name "/PORT17") (class "Default")
      (node (ref "U1") (pin "62") (pinfunction "PB9_62") (pintype "passive"))
    )
    (net (code "28") (name "/PORT18") (class "Default")
      (node (ref "U1") (pin "59") (pinfunction "PB7_59") (pintype "passive"))
    )
    (net (code "29") (name "/PORT19") (class "Default")
      (node (ref "U1") (pin "61") (pinfunction "PB8_61") (pintype "passive"))
    )
    (net (code "30") (name "/RESET") (class "Default")
      (node (ref "C3") (pin "2") (pinfunction "2_2") (pintype "passive"))
      (node (ref "P1") (pin "7") (pinfunction "7_7") (pintype "passive"))
      (node (ref "R58") (pin "1") (pinfunction "1_1") (pintype "passive"))
      (node (ref "U1") (pin "7") (pinfunction "NRST_7") (pintype "passive"))
    )
    (net (code "31") (name "/SCL") (class "Default")
      (node (ref "R94") (pin "1") (pinfunction "1_1") (pintype "passive"))
      (node (ref "U1") (pin "15") (pinfunction "RA1_15") (pintype "passive"))
      (node (ref "U4") (pin "6") (pinfunction "SCL_6") (pintype "passive"))
    )
    (net (code "32") (name "/SDA") (class "Default")
      (node (ref "R97") (pin "1") (pinfunction "1_1") (pintype "passive"))
      (node (ref "U1") (pin "14") (pinfunction "RA0/WKUP_14") (pintype "passive"))
      (node (ref "U4") (pin "5") (pinfunction "SDA_5") (pintype "passive"))
    )
    (net (code "33") (name "/SW1") (class "Default")
      (node (ref "R52") (pin "2") (pinfunction "2_2") (pintype "passive"))
      (node (ref "R54") (pin "2") (pinfunction "2_2") (pintype "passive"))
      (node (ref "U1") (pin "2") (pinfunction "PC13/TAMPER-RTC_2") (pintype "passive"))
    )
    (net (code "34") (name "/SW2") (class "Default")
      (node (ref "R53") (pin "2") (pinfunction "2_2") (pintype "passive"))
      (node (ref "R55") (pin "2") (pinfunction "2_2") (pintype "passive"))
      (node (ref "U1") (pin "3") (pinfunction "PC14/OSC32-IN_3") (pintype "passive"))
    )
    (net (code "35") (name "/SW3") (class "Default")
      (node (ref "R56") (pin "2") (pinfunction "2_2") (pintype "passive"))
      (node (ref "R59") (pin "2") (pinfunction "2_2") (pintype "passive"))
      (node (ref "U1") (pin "4") (pinfunction "PC15/OSC32-OUT_4") (pintype "passive"))
    )
    (net (code "36") (name "/SW4") (class "Default")
      (node (ref "R57") (pin "2") (pinfunction "2_2") (pintype "passive"))
      (node (ref "R60") (pin "2") (pinfunction "2_2") (pintype "passive"))
      (node (ref "U1") (pin "8") (pinfunction "PC0_8") (pintype "passive"))
    )
    (net (code "37") (name "/SW5") (class "Default")
      (node (ref "R61") (pin "2") (pinfunction "2_2") (pintype "passive"))
      (node (ref "R64") (pin "2") (pinfunction "2_2") (pintype "passive"))
      (node (ref "U1") (pin "9") (pinfunction "PC1_9") (pintype "passive"))
    )
    (net (code "38") (name "/SW6") (class "Default")
      (node (ref "R62") (pin "2") (pinfunction "2_2") (pintype "passive"))
      (node (ref "R65") (pin "2") (pinfunction "2_2") (pintype "passive"))
      (node (ref "U1") (pin "10") (pinfunction "PC2_10") (pintype "passive"))
    )
    (net (code "39") (name "/SW7") (class "Default")
      (node (ref "R66") (pin "2") (pinfunction "2_2") (pintype "passive"))
      (node (ref "R68") (pin "2") (pinfunction "2_2") (pintype "passive"))
      (node (ref "U1") (pin "11") (pinfunction "PC3_11") (pintype "passive"))
    )
    (net (code "40") (name "/SW8") (class "Default")
      (node (ref "R67") (pin "2") (pinfunction "2_2") (pintype "passive"))
      (node (ref "R69") (pin "2") (pinfunction "2_2") (pintype "passive"))
      (node (ref "U1") (pin "17") (pinfunction "PA3_17") (pintype "passive"))
    )
    (net (code "41") (name "/SW9") (class "Default")
      (node (ref "R70") (pin "2") (pinfunction "2_2") (pintype "passive"))
      (node (ref "R72") (pin "2") (pinfunction "2_2") (pintype "passive"))
      (node (ref "U1") (pin "20") (pinfunction "PA4_20") (pintype "passive"))
    )
    (net (code "42") (name "/SW10") (class "Default")
      (node (ref "R71") (pin "2") (pinfunction "2_2") (pintype "passive"))
      (node (ref "R73") (pin "2") (pinfunction "2_2") (pintype "passive"))
      (node (ref "U1") (pin "21") (pinfunction "PA5_21") (pintype "passive"))
    )
    (net (code "43") (name "/SW11") (class "Default")
      (node (ref "R74") (pin "2") (pinfunction "2_2") (pintype "passive"))
      (node (ref "R76") (pin "2") (pinfunction "2_2") (pintype "passive"))
      (node (ref "U1") (pin "22") (pinfunction "PA6_22") (pintype "passive"))
    )
    (net (code "44") (name "/SW12") (class "Default")
      (node (ref "R75") (pin "2") (pinfunction "2_2") (pintype "passive"))
      (node (ref "R77") (pin "2") (pinfunction "2_2") (pintype "passive"))
      (node (ref "U1") (pin "23") (pinfunction "PA7_23") (pintype "passive"))
    )
    (net (code "45") (name "/SW13") (class "Default")
      (node (ref "R78") (pin "2") (pinfunction "2_2") (pintype "passive"))
      (node (ref "R80") (pin "2") (pinfunction "2_2") (pintype "passive"))
      (node (ref "U1") (pin "24") (pinfunction "PC4_24") (pintype "passive"))
    )
    (net (code "46") (name "/SW14") (class "Default")
      (node (ref "R79") (pin "2") (pinfunction "2_2") (pintype "passive"))
      (node (ref "R81") (pin "2") (pinfunction "2_2") (pintype "passive"))
      (node (ref "U1") (pin "25") (pinfunction "PC5_25") (pintype "passive"))
    )
    (net (code "47") (name "/SW15") (class "Default")
      (node (ref "R82") (pin "2") (pinfunction "2_2") (pintype "passive"))
      (node (ref "R84") (pin "2") (pinfunction "2_2") (pintype "passive"))
      (node (ref "U1") (pin "26") (pinfunction "PB0_26") (pintype "passive"))
    )
    (net (code "48") (name "/SW16") (class "Default")
      (node (ref "R83") (pin "2") (pinfunction "2_2") (pintype "passive"))
      (node (ref "R85") (pin "2") (pinfunction "2_2") (pintype "passive"))
      (node (ref "U1") (pin "27") (pinfunction "PB1_27") (pintype "passive"))
    )
    (net (code "49") (name "/SW17") (class "Default")
      (node (ref "R86") (pin "2") (pinfunction "2_2") (pintype "passive"))
      (node (ref "R87") (pin "2") (pinfunction "2_2") (pintype "passive"))
      (node (ref "U1") (pin "28") (pinfunction "PB2_28") (pintype "passive"))
    )
    (net (code "50") (name "/SW18") (class "Default")
      (node (ref "R93") (pin "2") (pinfunction "2_2") (pintype "passive"))
      (node (ref "R96") (pin "2") (pinfunction "2_2") (pintype "passive"))
      (node (ref "U1") (pin "29") (pinfunction "PB10_29") (pintype "passive"))
    )
    (net (code "51") (name "/SW19") (class "Default")
      (node (ref "R98") (pin "2") (pinfunction "2_2") (pintype "passive"))
      (node (ref "R99") (pin "2") (pinfunction "2_2") (pintype "passive"))
      (node (ref "U1") (pin "30") (pinfunction "PB11_30") (pintype "passive"))
    )
    (net (code "52") (name "/WP") (class "Default")
      (node (ref "R95") (pin "1") (pinfunction "1_1") (pintype "passive"))
      (node (ref "U1") (pin "16") (pinfunction "RA2_16") (pintype "passive"))
      (node (ref "U4") (pin "7") (pinfunction "WP_7") (pintype "passive"))
    )
    (net (code "53") (name "GND") (class "Default")
      (node (ref "C1") (pin "2") (pinfunction "2_2") (pintype "passive"))
      (node (ref "C10") (pin "2") (pinfunction "2_2") (pintype "passive"))
      (node (ref "C11") (pin "2") (pinfunction "2_2") (pintype "passive"))
      (node (ref "C12") (pin "2") (pinfunction "2_2") (pintype "passive"))
      (node (ref "C13") (pin "2") (pinfunction "2_2") (pintype "passive"))
      (node (ref "C14") (pin "1") (pinfunction "1_1") (pintype "passive"))
      (node (ref "C15") (pin "2") (pinfunction "2_2") (pintype "passive"))
      (node (ref "C16") (pin "1") (pinfunction "1_1") (pintype "passive"))
      (node (ref "C2") (pin "2") (pinfunction "2_2") (pintype "passive"))
      (node (ref "C3") (pin "1") (pinfunction "1_1") (pintype "passive"))
      (node (ref "C4") (pin "2") (pinfunction "2_2") (pintype "passive"))
      (node (ref "C5") (pin "2") (pinfunction "2_2") (pintype "passive"))
      (node (ref "C6") (pin "2") (pinfunction "2_2") (pintype "passive"))
      (node (ref "C7") (pin "2") (pinfunction "2_2") (pintype "passive"))
      (node (ref "C8") (pin "2") (pinfunction "2_2") (pintype "passive"))
      (node (ref "C9") (pin "2") (pinfunction "2_2") (pintype "passive"))
      (node (ref "GND") (pin "1") (pinfunction "1_1") (pintype "passive"))
      (node (ref "GND") (pin "2") (pinfunction "2_2") (pintype "passive"))
      (node (ref "P1") (pin "8") (pinfunction "8_8") (pintype "passive"))
      (node (ref "R54") (pin "1") (pinfunction "1_1") (pintype "passive"))
      (node (ref "R55") (pin "1") (pinfunction "1_1") (pintype "passive"))
      (node (ref "R59") (pin "1") (pinfunction "1_1") (pintype "passive"))
      (node (ref "R60") (pin "1") (pinfunction "1_1") (pintype "passive"))
      (node (ref "R64") (pin "1") (pinfunction "1_1") (pintype "passive"))
      (node (ref "R65") (pin "1") (pinfunction "1_1") (pintype "passive"))
      (node (ref "R68") (pin "1") (pinfunction "1_1") (pintype "passive"))
      (node (ref "R69") (pin "1") (pinfunction "1_1") (pintype "passive"))
      (node (ref "R72") (pin "1") (pinfunction "1_1") (pintype "passive"))
      (node (ref "R73") (pin "1") (pinfunction "1_1") (pintype "passive"))
      (node (ref "R76") (pin "1") (pinfunction "1_1") (pintype "passive"))
      (node (ref "R77") (pin "1") (pinfunction "1_1") (pintype "passive"))
      (node (ref "R80") (pin "1") (pinfunction "1_1") (pintype "passive"))
      (node (ref "R81") (pin "1") (pinfunction "1_1") (pintype "passive"))
      (node (ref "R84") (pin "1") (pinfunction "1_1") (pintype "passive"))
      (node (ref "R85") (pin "1") (pinfunction "1_1") (pintype "passive"))
      (node (ref "R87") (pin "1") (pinfunction "1_1") (pintype "passive"))
      (node (ref "R96") (pin "1") (pinfunction "1_1") (pintype "passive"))
      (node (ref "R99") (pin "1") (pinfunction "1_1") (pintype "passive"))
      (node (ref "U1") (pin "12") (pinfunction "VSSA_12") (pintype "passive"))
      (node (ref "U1") (pin "18") (pinfunction "VSS_4_18") (pintype "passive"))
      (node (ref "U1") (pin "31") (pinfunction "VSS_1_31") (pintype "passive"))
      (node (ref "U1") (pin "47") (pinfunction "VSS_2_47") (pintype "passive"))
      (node (ref "U1") (pin "60") (pinfunction "BOOT0_60") (pintype "passive"))
      (node (ref "U1") (pin "63") (pinfunction "VSS_3_63") (pintype "passive"))
      (node (ref "U2") (pin "1") (pinfunction "GND_1") (pintype "passive"))
      (node (ref "U3") (pin "1") (pinfunction "1_1") (pintype "passive"))
      (node (ref "U3") (pin "7") (pinfunction "7_7") (pintype "passive"))
      (node (ref "U4") (pin "1") (pinfunction "A0_1") (pintype "passive"))
      (node (ref "U4") (pin "2") (pinfunction "A1_2") (pintype "passive"))
      (node (ref "U4") (pin "3") (pinfunction "A2_3") (pintype "passive"))
      (node (ref "U4") (pin "4") (pinfunction "GND_4") (pintype "passive"))
    )
    (net (code "54") (name "Net-(C14-Pad2)") (class "Default")
      (node (ref "C14") (pin "2") (pinfunction "2_2") (pintype "passive"))
      (node (ref "L1") (pin "2") (pinfunction "2_2") (pintype "passive"))
      (node (ref "U3") (pin "2") (pinfunction "2_2") (pintype "passive"))
    )
    (net (code "55") (name "Net-(C16-Pad2)") (class "Default")
      (node (ref "C16") (pin "2") (pinfunction "2_2") (pintype "passive"))
      (node (ref "U3") (pin "8") (pinfunction "8_8") (pintype "passive"))
    )
    (net (code "56") (name "Net-(F1-Pad1)") (class "Default")
      (node (ref "F1") (pin "1") (pinfunction "1_1") (pintype "passive"))
      (node (ref "P5") (pin "3") (pinfunction "3_3") (pintype "passive"))
    )
    (net (code "57") (name "Net-(F1-Pad2)") (class "Default")
      (node (ref "F1") (pin "2") (pinfunction "2_2") (pintype "passive"))
      (node (ref "L") (pin "1") (pinfunction "1_1") (pintype "passive"))
    )
    (net (code "58") (name "Net-(FG-Pad1)") (class "Default")
      (node (ref "FG") (pin "1") (pinfunction "1_1") (pintype "passive"))
      (node (ref "P5") (pin "2") (pinfunction "2_2") (pintype "passive"))
    )
    (net (code "59") (name "Net-(N-Pad1)") (class "Default")
      (node (ref "N") (pin "1") (pinfunction "1_1") (pintype "passive"))
      (node (ref "P5") (pin "1") (pinfunction "1_1") (pintype "passive"))
    )
    (net (code "60") (name "Net-(R52-Pad1)") (class "Default")
      (node (ref "R52") (pin "1") (pinfunction "1_1") (pintype "passive"))
      (node (ref "S1") (pin "2") (pinfunction "2_2") (pintype "passive"))
      (node (ref "S1") (pin "3") (pinfunction "3_3") (pintype "passive"))
    )
    (net (code "61") (name "Net-(R53-Pad1)") (class "Default")
      (node (ref "R53") (pin "1") (pinfunction "1_1") (pintype "passive"))
      (node (ref "S2") (pin "2") (pinfunction "2_2") (pintype "passive"))
      (node (ref "S2") (pin "3") (pinfunction "3_3") (pintype "passive"))
    )
    (net (code "62") (name "Net-(R56-Pad1)") (class "Default")
      (node (ref "R56") (pin "1") (pinfunction "1_1") (pintype "passive"))
      (node (ref "S3") (pin "2") (pinfunction "2_2") (pintype "passive"))
      (node (ref "S3") (pin "3") (pinfunction "3_3") (pintype "passive"))
    )
    (net (code "63") (name "Net-(R57-Pad1)") (class "Default")
      (node (ref "R57") (pin "1") (pinfunction "1_1") (pintype "passive"))
      (node (ref "S4") (pin "2") (pinfunction "2_2") (pintype "passive"))
      (node (ref "S4") (pin "3") (pinfunction "3_3") (pintype "passive"))
    )
    (net (code "64") (name "Net-(R61-Pad1)") (class "Default")
      (node (ref "R61") (pin "1") (pinfunction "1_1") (pintype "passive"))
      (node (ref "S5") (pin "2") (pinfunction "2_2") (pintype "passive"))
      (node (ref "S5") (pin "3") (pinfunction "3_3") (pintype "passive"))
    )
    (net (code "65") (name "Net-(R62-Pad1)") (class "Default")
      (node (ref "R62") (pin "1") (pinfunction "1_1") (pintype "passive"))
      (node (ref "S6") (pin "2") (pinfunction "2_2") (pintype "passive"))
      (node (ref "S6") (pin "3") (pinfunction "3_3") (pintype "passive"))
    )
    (net (code "66") (name "Net-(R66-Pad1)") (class "Default")
      (node (ref "R66") (pin "1") (pinfunction "1_1") (pintype "passive"))
      (node (ref "S7") (pin "2") (pinfunction "2_2") (pintype "passive"))
      (node (ref "S7") (pin "3") (pinfunction "3_3") (pintype "passive"))
    )
    (net (code "67") (name "Net-(R67-Pad1)") (class "Default")
      (node (ref "R67") (pin "1") (pinfunction "1_1") (pintype "passive"))
      (node (ref "S8") (pin "2") (pinfunction "2_2") (pintype "passive"))
      (node (ref "S8") (pin "3") (pinfunction "3_3") (pintype "passive"))
    )
    (net (code "68") (name "Net-(R70-Pad1)") (class "Default")
      (node (ref "R70") (pin "1") (pinfunction "1_1") (pintype "passive"))
      (node (ref "S9") (pin "2") (pinfunction "2_2") (pintype "passive"))
      (node (ref "S9") (pin "3") (pinfunction "3_3") (pintype "passive"))
    )
    (net (code "69") (name "Net-(R71-Pad1)") (class "Default")
      (node (ref "R71") (pin "1") (pinfunction "1_1") (pintype "passive"))
      (node (ref "S10") (pin "2") (pinfunction "2_2") (pintype "passive"))
      (node (ref "S10") (pin "3") (pinfunction "3_3") (pintype "passive"))
    )
    (net (code "70") (name "Net-(R74-Pad1)") (class "Default")
      (node (ref "R74") (pin "1") (pinfunction "1_1") (pintype "passive"))
      (node (ref "S11") (pin "2") (pinfunction "2_2") (pintype "passive"))
      (node (ref "S11") (pin "3") (pinfunction "3_3") (pintype "passive"))
    )
    (net (code "71") (name "Net-(R75-Pad1)") (class "Default")
      (node (ref "R75") (pin "1") (pinfunction "1_1") (pintype "passive"))
      (node (ref "S12") (pin "2") (pinfunction "2_2") (pintype "passive"))
      (node (ref "S12") (pin "3") (pinfunction "3_3") (pintype "passive"))
    )
    (net (code "72") (name "Net-(R78-Pad1)") (class "Default")
      (node (ref "R78") (pin "1") (pinfunction "1_1") (pintype "passive"))
      (node (ref "S13") (pin "2") (pinfunction "2_2") (pintype "passive"))
      (node (ref "S13") (pin "3") (pinfunction "3_3") (pintype "passive"))
    )
    (net (code "73") (name "Net-(R79-Pad1)") (class "Default")
      (node (ref "R79") (pin "1") (pinfunction "1_1") (pintype "passive"))
      (node (ref "S14") (pin "2") (pinfunction "2_2") (pintype "passive"))
      (node (ref "S14") (pin "3") (pinfunction "3_3") (pintype "passive"))
    )
    (net (code "74") (name "Net-(R82-Pad1)") (class "Default")
      (node (ref "R82") (pin "1") (pinfunction "1_1") (pintype "passive"))
      (node (ref "S15") (pin "2") (pinfunction "2_2") (pintype "passive"))
      (node (ref "S15") (pin "3") (pinfunction "3_3") (pintype "passive"))
    )
    (net (code "75") (name "Net-(R83-Pad1)") (class "Default")
      (node (ref "R83") (pin "1") (pinfunction "1_1") (pintype "passive"))
      (node (ref "S16") (pin "2") (pinfunction "2_2") (pintype "passive"))
      (node (ref "S16") (pin "3") (pinfunction "3_3") (pintype "passive"))
    )
    (net (code "76") (name "Net-(R86-Pad1)") (class "Default")
      (node (ref "R86") (pin "1") (pinfunction "1_1") (pintype "passive"))
      (node (ref "S17") (pin "2") (pinfunction "2_2") (pintype "passive"))
      (node (ref "S17") (pin "3") (pinfunction "3_3") (pintype "passive"))
    )
    (net (code "77") (name "Net-(R93-Pad1)") (class "Default")
      (node (ref "R93") (pin "1") (pinfunction "1_1") (pintype "passive"))
      (node (ref "S18") (pin "2") (pinfunction "2_2") (pintype "passive"))
      (node (ref "S18") (pin "3") (pinfunction "3_3") (pintype "passive"))
    )
    (net (code "78") (name "Net-(R98-Pad1)") (class "Default")
      (node (ref "R98") (pin "1") (pinfunction "1_1") (pintype "passive"))
      (node (ref "S19") (pin "2") (pinfunction "2_2") (pintype "passive"))
      (node (ref "S19") (pin "3") (pinfunction "3_3") (pintype "passive"))
    )
    (net (code "79") (name "Net-(U1-PD0{slash}OSC_IN)") (class "Default")
      (node (ref "C1") (pin "1") (pinfunction "1_1") (pintype "passive"))
      (node (ref "R63") (pin "1") (pinfunction "1_1") (pintype "passive"))
      (node (ref "U1") (pin "5") (pinfunction "PD0/OSC_IN_5") (pintype "passive"))
      (node (ref "X1") (pin "2") (pinfunction "OSC2_2") (pintype "passive"))
    )
    (net (code "80") (name "Net-(U1-PD0{slash}OSC_OUT)") (class "Default")
      (node (ref "C2") (pin "1") (pinfunction "1_1") (pintype "passive"))
      (node (ref "R63") (pin "2") (pinfunction "2_2") (pintype "passive"))
      (node (ref "U1") (pin "6") (pinfunction "PD0/OSC_OUT_6") (pintype "passive"))
      (node (ref "X1") (pin "1") (pinfunction "OSC1_1") (pintype "passive"))
    )
    (net (code "81") (name "unconnected-(U1-PB5-Pad57)") (class "Default")
      (node (ref "U1") (pin "57") (pinfunction "PB5_57") (pintype "passive"))
    )
    (net (code "82") (name "unconnected-(U3-Pad3)") (class "Default")
      (node (ref "U3") (pin "3") (pinfunction "3_3") (pintype "passive"))
    )
    (net (code "83") (name "unconnected-(U3-Pad5)") (class "Default")
      (node (ref "U3") (pin "5") (pinfunction "5_5") (pintype "passive"))
    )
  )
)
